# FidoBark.net
KiCad netlist of a schematic drawn in EAGLE
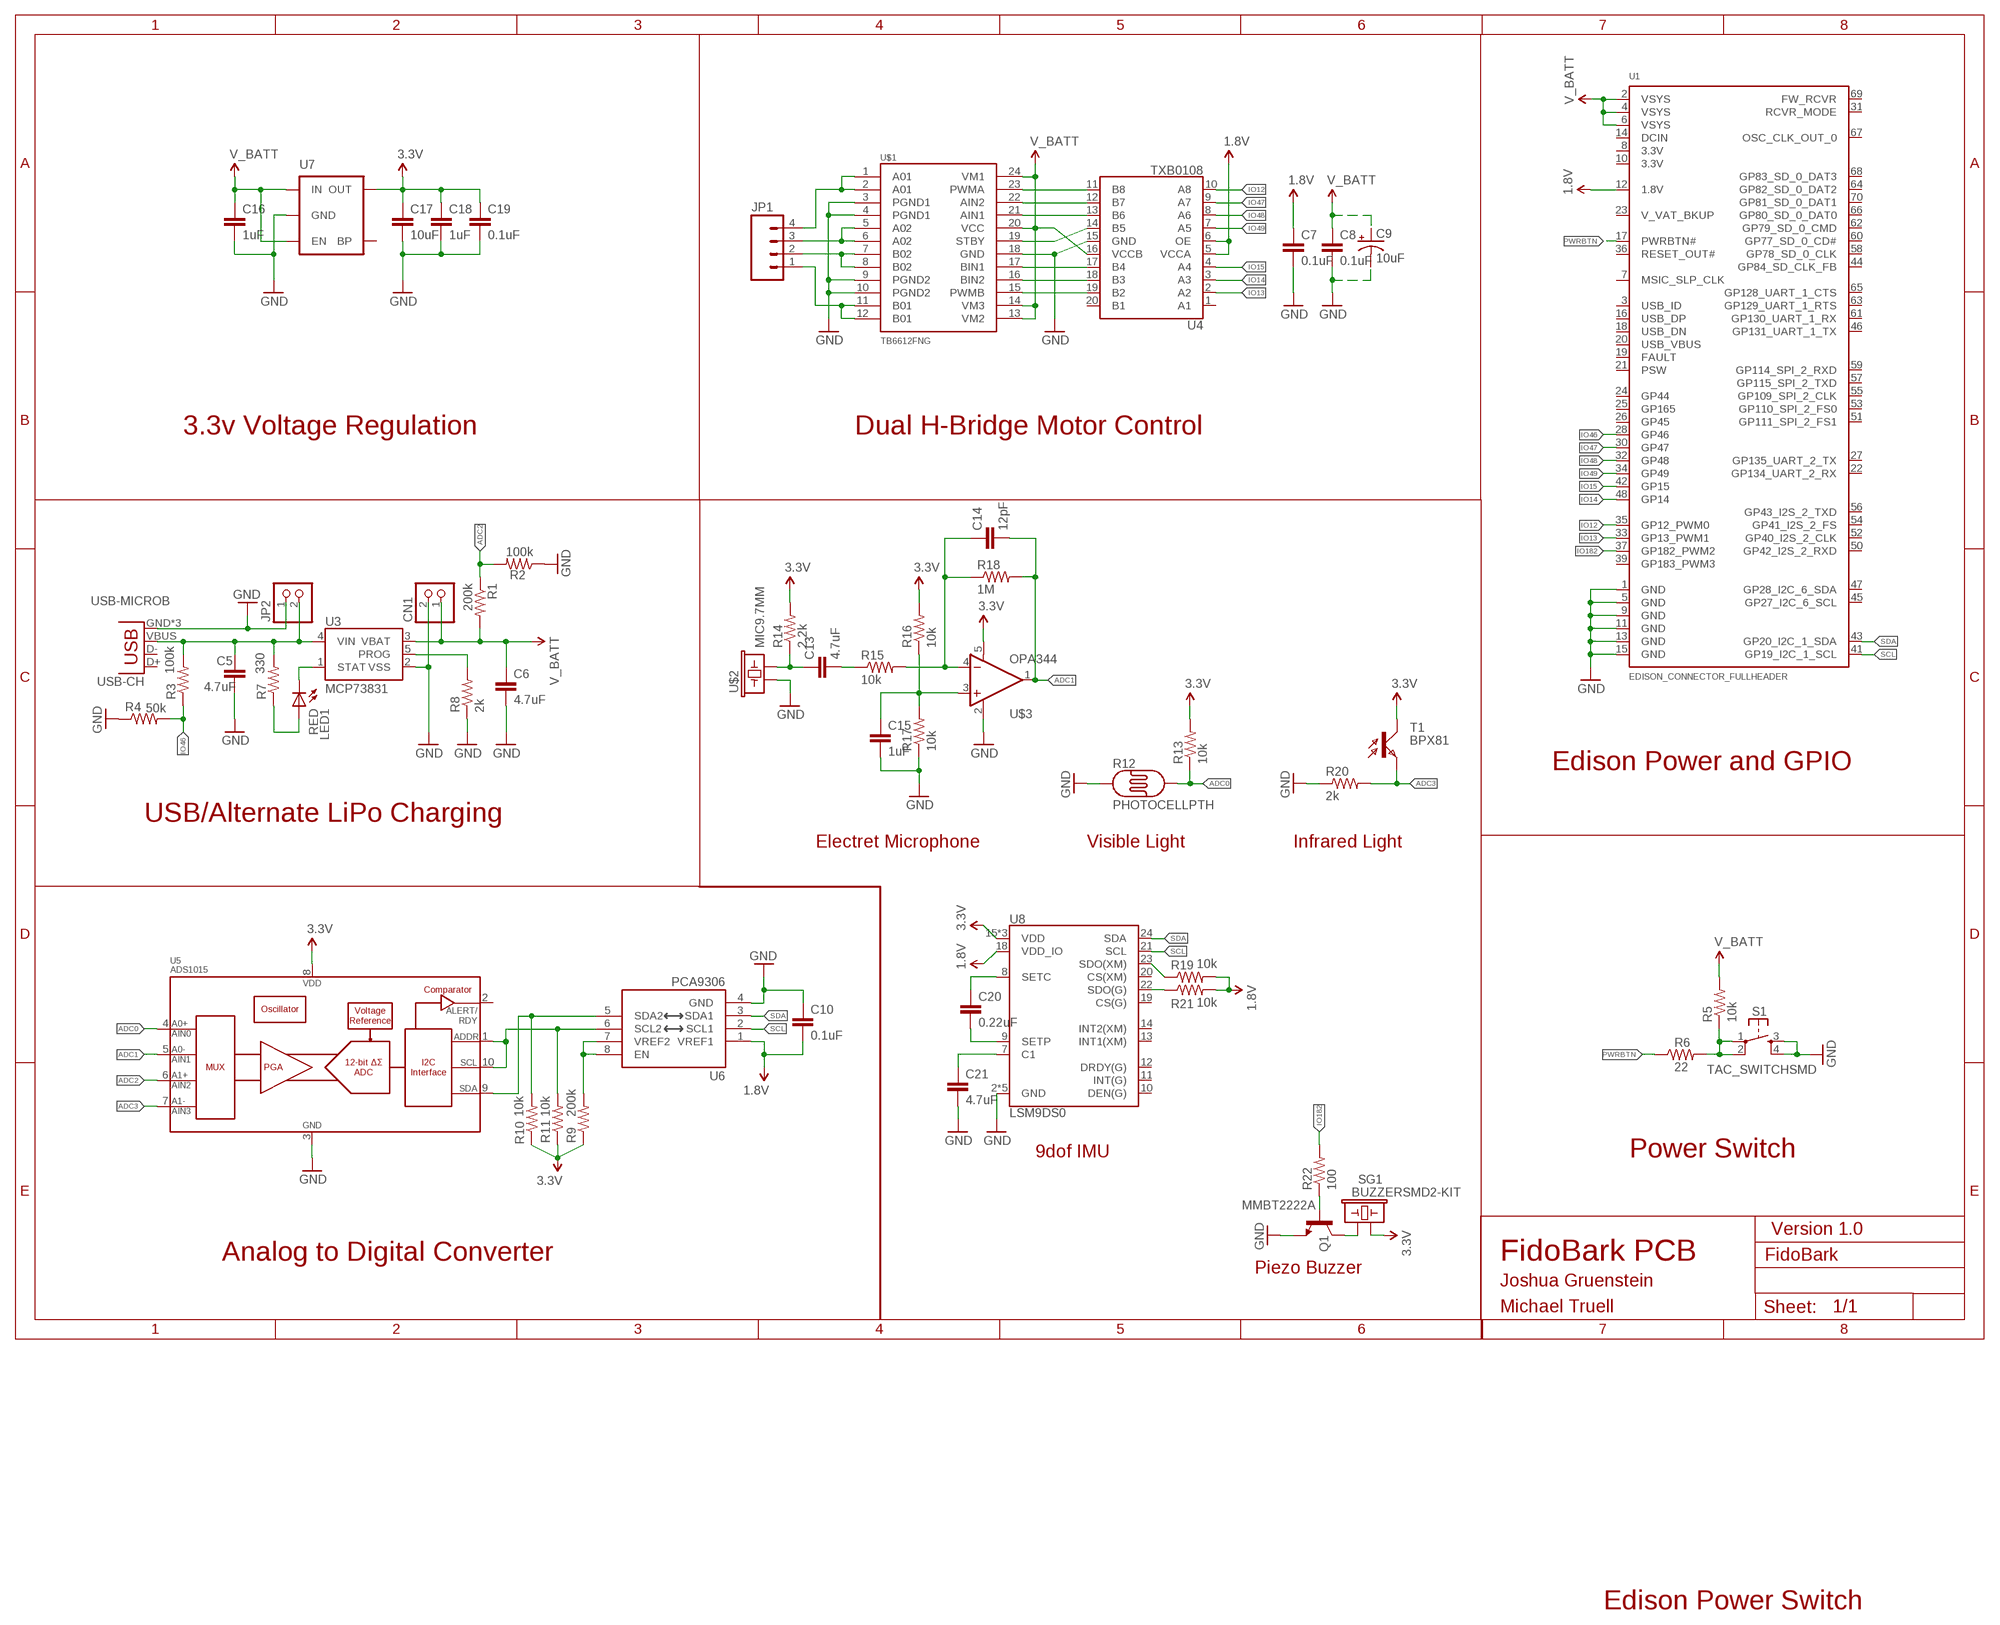
[diagram p0: schematic, sheet 1]

(export (version "E")
  (design (tool "Eeschema 10.0.6"))
  (components
    (comp (ref "C5")
      (value "4.7uF")
      (footprint "eagle-import:0603-CAP")
      (libsource (lib "eagle-import") (part "SparkFun-Passives_CAP0603-CAP"))
    )
    (comp (ref "C6")
      (value "4.7uF")
      (footprint "eagle-import:0603-CAP")
      (libsource (lib "eagle-import") (part "SparkFun-Passives_CAP0603-CAP"))
    )
    (comp (ref "C7")
      (value "0.1uF")
      (footprint "eagle-import:0603-CAP")
      (libsource (lib "eagle-import") (part "CAP0603-CAP"))
    )
    (comp (ref "C8")
      (value "0.1uF")
      (footprint "eagle-import:0603-CAP")
      (libsource (lib "eagle-import") (part "CAP0603-CAP"))
    )
    (comp (ref "C9")
      (value "10uF")
      (footprint "eagle-import:EIA3216")
      (libsource (lib "eagle-import") (part "CAP_POL1206"))
    )
    (comp (ref "C10")
      (value "0.1uF")
      (footprint "eagle-import:0603-CAP")
      (libsource (lib "eagle-import") (part "SparkFun-Passives_CAP0603-CAP"))
    )
    (comp (ref "C13")
      (value "4.7uF")
      (footprint "eagle-import:0603-CAP")
      (libsource (lib "eagle-import") (part "SparkFun-Passives_CAP0603-CAP"))
    )
    (comp (ref "C14")
      (value "12pF")
      (footprint "eagle-import:0603-CAP")
      (libsource (lib "eagle-import") (part "SparkFun-Passives_CAP0603-CAP"))
    )
    (comp (ref "C15")
      (value "1uF")
      (footprint "eagle-import:0603-CAP")
      (libsource (lib "eagle-import") (part "SparkFun-Passives_CAP0603-CAP"))
    )
    (comp (ref "C16")
      (value "1uF")
      (footprint "eagle-import:0603-CAP")
      (libsource (lib "eagle-import") (part "SparkFun-Passives_CAP0603-CAP"))
    )
    (comp (ref "C17")
      (value "10uF")
      (footprint "eagle-import:0603-CAP")
      (libsource (lib "eagle-import") (part "SparkFun-Passives_CAP0603-CAP"))
    )
    (comp (ref "C18")
      (value "1uF")
      (footprint "eagle-import:0603-CAP")
      (libsource (lib "eagle-import") (part "SparkFun-Passives_CAP0603-CAP"))
    )
    (comp (ref "C19")
      (value "0.1uF")
      (footprint "eagle-import:0603-CAP")
      (libsource (lib "eagle-import") (part "SparkFun-Passives_CAP0603-CAP"))
    )
    (comp (ref "C20")
      (value "0.22uF")
      (footprint "eagle-import:0603-CAP")
      (libsource (lib "eagle-import") (part "SparkFun-Passives_CAP0603-CAP"))
    )
    (comp (ref "C21")
      (value "4.7uF")
      (footprint "eagle-import:0603-CAP")
      (libsource (lib "eagle-import") (part "SparkFun-Passives_CAP0603-CAP"))
    )
    (comp (ref "CN1")
      (value "JST_2PIN-SMT-RA")
      (footprint "eagle-import:JST-PH-2-SMT-RA")
      (libsource (lib "eagle-import") (part "JST_2PIN-SMT-RA"))
    )
    (comp (ref "JP1")
      (value "M04PTH")
      (footprint "eagle-import:1X04")
      (libsource (lib "eagle-import") (part "M04PTH"))
    )
    (comp (ref "JP2")
      (value "PINHD-1X2")
      (footprint "eagle-import:1X02")
      (libsource (lib "eagle-import") (part "PINHD-1X2"))
    )
    (comp (ref "LED1")
      (value "RED")
      (footprint "eagle-import:CHIP-LED0603")
      (libsource (lib "eagle-import") (part "LEDCHIP-LED0603"))
    )
    (comp (ref "Q1")
      (value "MMBT2222A")
      (footprint "eagle-import:SOT23-3")
      (libsource (lib "eagle-import") (part "TRANSISTOR_NPNMMBT2222A"))
    )
    (comp (ref "R1")
      (value "200k")
      (footprint "eagle-import:R0603")
      (libsource (lib "eagle-import") (part "R-US_R0603"))
    )
    (comp (ref "R2")
      (value "100k")
      (footprint "eagle-import:R0603")
      (libsource (lib "eagle-import") (part "R-US_R0603"))
    )
    (comp (ref "R3")
      (value "100k")
      (footprint "eagle-import:R0603")
      (libsource (lib "eagle-import") (part "R-US_R0603"))
    )
    (comp (ref "R4")
      (value "50k")
      (footprint "eagle-import:R0603")
      (libsource (lib "eagle-import") (part "R-US_R0603"))
    )
    (comp (ref "R5")
      (value "10k")
      (footprint "eagle-import:R0603")
      (libsource (lib "eagle-import") (part "R-US_R0603"))
    )
    (comp (ref "R6")
      (value "22")
      (footprint "eagle-import:R0603")
      (libsource (lib "eagle-import") (part "R-US_R0603"))
    )
    (comp (ref "R7")
      (value "330")
      (footprint "eagle-import:R0603")
      (libsource (lib "eagle-import") (part "R-US_R0603"))
    )
    (comp (ref "R8")
      (value "2k")
      (footprint "eagle-import:R0603")
      (libsource (lib "eagle-import") (part "R-US_R0603"))
    )
    (comp (ref "R9")
      (value "200k")
      (footprint "eagle-import:R0603")
      (libsource (lib "eagle-import") (part "R-US_R0603"))
    )
    (comp (ref "R10")
      (value "10k")
      (footprint "eagle-import:R0603")
      (libsource (lib "eagle-import") (part "R-US_R0603"))
    )
    (comp (ref "R11")
      (value "10k")
      (footprint "eagle-import:R0603")
      (libsource (lib "eagle-import") (part "R-US_R0603"))
    )
    (comp (ref "R12")
      (value "PHOTOCELLPTH")
      (footprint "eagle-import:PHOTOCELL")
      (libsource (lib "eagle-import") (part "PHOTOCELLPTH"))
    )
    (comp (ref "R13")
      (value "10k")
      (footprint "eagle-import:R0603")
      (libsource (lib "eagle-import") (part "R-US_R0603"))
    )
    (comp (ref "R14")
      (value "2.2k")
      (footprint "eagle-import:R0603")
      (libsource (lib "eagle-import") (part "R-US_R0603"))
    )
    (comp (ref "R15")
      (value "10k")
      (footprint "eagle-import:R0603")
      (libsource (lib "eagle-import") (part "R-US_R0603"))
    )
    (comp (ref "R16")
      (value "10k")
      (footprint "eagle-import:R0603")
      (libsource (lib "eagle-import") (part "R-US_R0603"))
    )
    (comp (ref "R17")
      (value "10k")
      (footprint "eagle-import:R0603")
      (libsource (lib "eagle-import") (part "R-US_R0603"))
    )
    (comp (ref "R18")
      (value "1M")
      (footprint "eagle-import:R0603")
      (libsource (lib "eagle-import") (part "R-US_R0603"))
    )
    (comp (ref "R19")
      (value "10k")
      (footprint "eagle-import:R0603")
      (libsource (lib "eagle-import") (part "R-US_R0603"))
    )
    (comp (ref "R20")
      (value "2k")
      (footprint "eagle-import:R0603")
      (libsource (lib "eagle-import") (part "R-US_R0603"))
    )
    (comp (ref "R21")
      (value "10k")
      (footprint "eagle-import:R0603")
      (libsource (lib "eagle-import") (part "R-US_R0603"))
    )
    (comp (ref "R22")
      (value "100")
      (footprint "eagle-import:R0603")
      (libsource (lib "eagle-import") (part "R-US_R0603"))
    )
    (comp (ref "S1")
      (value "TAC_SWITCHSMD")
      (footprint "eagle-import:TACTILE-SWITCH-SMD")
      (libsource (lib "eagle-import") (part "TAC_SWITCHSMD"))
    )
    (comp (ref "SG1")
      (value "BUZZERSMD2-KIT")
      (footprint "eagle-import:BUZZER-CCV-KIT")
      (libsource (lib "eagle-import") (part "BUZZERSMD2-KIT"))
    )
    (comp (ref "T1")
      (value "BPX81")
      (footprint "eagle-import:BPX81")
      (libsource (lib "eagle-import") (part "BPX81"))
    )
    (comp (ref "U$1")
      (value "TB6612FNG")
      (footprint "eagle-import:SSOP24")
      (libsource (lib "eagle-import") (part "TB6612FNG"))
    )
    (comp (ref "U$2")
      (value "MIC9.7MM")
      (footprint "eagle-import:MIC-9.7MM")
      (libsource (lib "eagle-import") (part "MIC9.7MM"))
    )
    (comp (ref "U$3")
      (value "OPA344")
      (footprint "eagle-import:SOT23-5")
      (libsource (lib "eagle-import") (part "OPA344"))
    )
    (comp (ref "U1")
      (value "EDISON_CONNECTOR_FULLHEADER")
      (footprint "eagle-import:DF40C-70DP-0.4(51)")
      (libsource (lib "eagle-import") (part "EDISON_CONNECTOR_FULLHEADER"))
    )
    (comp (ref "U3")
      (value "MCP73831")
      (footprint "eagle-import:SOT23-5")
      (libsource (lib "eagle-import") (part "MCP73831"))
    )
    (comp (ref "U4")
      (value "TXB0108")
      (footprint "eagle-import:UFDFN-20")
      (libsource (lib "eagle-import") (part "TXB0108"))
    )
    (comp (ref "U5")
      (value "ADS1015")
      (footprint "eagle-import:MSOP10")
      (libsource (lib "eagle-import") (part "ADS1015"))
    )
    (comp (ref "U6")
      (value "PCA9306")
      (footprint "eagle-import:PSOP-8")
      (libsource (lib "eagle-import") (part "PCA9306"))
    )
    (comp (ref "U7")
      (value "MIC52053.3V")
      (footprint "eagle-import:SOT23-5")
      (libsource (lib "eagle-import") (part "MIC52053.3V"))
    )
    (comp (ref "U8")
      (value "LSM9DS0")
      (footprint "eagle-import:LGA-24")
      (libsource (lib "eagle-import") (part "LSM9DS0"))
    )
    (comp (ref "USB-CH")
      (value "USB-MICROB")
      (footprint "eagle-import:USB-MICROB")
      (libsource (lib "eagle-import") (part "USB-MICROB"))
    )
  )
  (nets
    (net (code "1") (name "1.8V") (class "Default")
      (node (ref "C10") (pin "2") (pinfunction "2_2") (pintype "passive"))
      (node (ref "C7") (pin "1") (pinfunction "1_1") (pintype "passive"))
      (node (ref "R19") (pin "2") (pinfunction "2_2") (pintype "passive"))
      (node (ref "R21") (pin "2") (pinfunction "2_2") (pintype "passive"))
      (node (ref "U1") (pin "12") (pinfunction "1.8V_12") (pintype "bidirectional"))
      (node (ref "U4") (pin "5") (pinfunction "VCCA_5") (pintype "bidirectional"))
      (node (ref "U4") (pin "6") (pinfunction "OE_6") (pintype "bidirectional"))
      (node (ref "U6") (pin "1") (pinfunction "VREF1_1") (pintype "bidirectional"))
      (node (ref "U8") (pin "18") (pinfunction "VDD_IO_18") (pintype "bidirectional"))
    )
    (net (code "2") (name "3.3V") (class "Default")
      (node (ref "C17") (pin "1") (pinfunction "1_1") (pintype "passive"))
      (node (ref "C18") (pin "1") (pinfunction "1_1") (pintype "passive"))
      (node (ref "C19") (pin "1") (pinfunction "1_1") (pintype "passive"))
      (node (ref "R10") (pin "1") (pinfunction "1_1") (pintype "passive"))
      (node (ref "R11") (pin "1") (pinfunction "1_1") (pintype "passive"))
      (node (ref "R13") (pin "2") (pinfunction "2_2") (pintype "passive"))
      (node (ref "R14") (pin "2") (pinfunction "2_2") (pintype "passive"))
      (node (ref "R16") (pin "2") (pinfunction "2_2") (pintype "passive"))
      (node (ref "R9") (pin "1") (pinfunction "1_1") (pintype "passive"))
      (node (ref "SG1") (pin "-") (pinfunction "2_-") (pintype "passive"))
      (node (ref "T1") (pin "C") (pinfunction "C_C") (pintype "passive"))
      (node (ref "U$3") (pin "5") (pinfunction "V+_5") (pintype "power_in"))
      (node (ref "U5") (pin "8") (pinfunction "VDD_8") (pintype "bidirectional"))
      (node (ref "U7") (pin "5") (pinfunction "OUT_5") (pintype "passive"))
      (node (ref "U8") (pin "15") (pinfunction "VDD_15") (pintype "bidirectional"))
      (node (ref "U8") (pin "16") (pinfunction "VDD_16") (pintype "bidirectional"))
      (node (ref "U8") (pin "17") (pinfunction "VDD_17") (pintype "bidirectional"))
    )
    (net (code "3") (name "ADC0") (class "Default")
      (node (ref "R12") (pin "2") (pinfunction "P$2_2") (pintype "bidirectional"))
      (node (ref "R13") (pin "1") (pinfunction "1_1") (pintype "passive"))
      (node (ref "U5") (pin "4") (pinfunction "AIN0_4") (pintype "bidirectional"))
    )
    (net (code "4") (name "ADC1") (class "Default")
      (node (ref "C14") (pin "2") (pinfunction "2_2") (pintype "passive"))
      (node (ref "R18") (pin "2") (pinfunction "2_2") (pintype "passive"))
      (node (ref "U$3") (pin "1") (pinfunction "OUT_1") (pintype "output"))
      (node (ref "U5") (pin "5") (pinfunction "AIN1_5") (pintype "bidirectional"))
    )
    (net (code "5") (name "ADC2") (class "Default")
      (node (ref "R1") (pin "1") (pinfunction "1_1") (pintype "passive"))
      (node (ref "R2") (pin "2") (pinfunction "2_2") (pintype "passive"))
      (node (ref "U5") (pin "6") (pinfunction "AIN2_6") (pintype "bidirectional"))
    )
    (net (code "6") (name "ADC3") (class "Default")
      (node (ref "R20") (pin "2") (pinfunction "2_2") (pintype "passive"))
      (node (ref "T1") (pin "E") (pinfunction "E_E") (pintype "passive"))
      (node (ref "U5") (pin "7") (pinfunction "AIN3_7") (pintype "bidirectional"))
    )
    (net (code "7") (name "GND") (class "Default")
      (node (ref "C10") (pin "1") (pinfunction "1_1") (pintype "passive"))
      (node (ref "C15") (pin "2") (pinfunction "2_2") (pintype "passive"))
      (node (ref "C16") (pin "2") (pinfunction "2_2") (pintype "passive"))
      (node (ref "C17") (pin "2") (pinfunction "2_2") (pintype "passive"))
      (node (ref "C18") (pin "2") (pinfunction "2_2") (pintype "passive"))
      (node (ref "C19") (pin "2") (pinfunction "2_2") (pintype "passive"))
      (node (ref "C21") (pin "2") (pinfunction "2_2") (pintype "passive"))
      (node (ref "C5") (pin "2") (pinfunction "2_2") (pintype "passive"))
      (node (ref "C6") (pin "2") (pinfunction "2_2") (pintype "passive"))
      (node (ref "C7") (pin "2") (pinfunction "2_2") (pintype "passive"))
      (node (ref "C8") (pin "2") (pinfunction "2_2") (pintype "passive"))
      (node (ref "C9") (pin "C") (pinfunction "-_C") (pintype "passive"))
      (node (ref "CN1") (pin "2") (pinfunction "1_2") (pintype "passive"))
      (node (ref "JP2") (pin "1") (pinfunction "1_1") (pintype "passive"))
      (node (ref "Q1") (pin "2") (pinfunction "E_2") (pintype "passive"))
      (node (ref "R12") (pin "1") (pinfunction "P$1_1") (pintype "bidirectional"))
      (node (ref "R17") (pin "1") (pinfunction "1_1") (pintype "passive"))
      (node (ref "R2") (pin "1") (pinfunction "1_1") (pintype "passive"))
      (node (ref "R20") (pin "1") (pinfunction "1_1") (pintype "passive"))
      (node (ref "R4") (pin "1") (pinfunction "1_1") (pintype "passive"))
      (node (ref "R8") (pin "1") (pinfunction "1_1") (pintype "passive"))
      (node (ref "S1") (pin "3") (pinfunction "3_3") (pintype "passive"))
      (node (ref "S1") (pin "4") (pinfunction "4_4") (pintype "passive"))
      (node (ref "U$1") (pin "10") (pinfunction "PGND2_10") (pintype "bidirectional"))
      (node (ref "U$1") (pin "18") (pinfunction "GND_18") (pintype "bidirectional"))
      (node (ref "U$1") (pin "3") (pinfunction "PGND1_3") (pintype "bidirectional"))
      (node (ref "U$1") (pin "4") (pinfunction "PGND1_4") (pintype "bidirectional"))
      (node (ref "U$1") (pin "9") (pinfunction "PGND2_9") (pintype "bidirectional"))
      (node (ref "U$2") (pin "1") (pinfunction "1_1") (pintype "passive"))
      (node (ref "U$3") (pin "2") (pinfunction "V-_2") (pintype "power_in"))
      (node (ref "U1") (pin "1") (pinfunction "GND_1") (pintype "bidirectional"))
      (node (ref "U1") (pin "11") (pinfunction "GND_11") (pintype "bidirectional"))
      (node (ref "U1") (pin "13") (pinfunction "GND_13") (pintype "bidirectional"))
      (node (ref "U1") (pin "15") (pinfunction "GND_15") (pintype "bidirectional"))
      (node (ref "U1") (pin "5") (pinfunction "GND_5") (pintype "bidirectional"))
      (node (ref "U1") (pin "9") (pinfunction "GND_9") (pintype "bidirectional"))
      (node (ref "U3") (pin "2") (pinfunction "VSS_2") (pintype "power_in"))
      (node (ref "U4") (pin "15") (pinfunction "GND_15") (pintype "bidirectional"))
      (node (ref "U5") (pin "3") (pinfunction "VSS_3") (pintype "bidirectional"))
      (node (ref "U6") (pin "4") (pinfunction "GND_4") (pintype "bidirectional"))
      (node (ref "U7") (pin "2") (pinfunction "GND_2") (pintype "input"))
      (node (ref "U8") (pin "2") (pinfunction "GND_2") (pintype "bidirectional"))
      (node (ref "U8") (pin "3") (pinfunction "GND_3") (pintype "bidirectional"))
      (node (ref "U8") (pin "4") (pinfunction "GND_4") (pintype "bidirectional"))
      (node (ref "U8") (pin "5") (pinfunction "GND_5") (pintype "bidirectional"))
      (node (ref "U8") (pin "6") (pinfunction "GND_6") (pintype "bidirectional"))
      (node (ref "USB-CH") (pin "GND") (pinfunction "GND_GND") (pintype "bidirectional"))
      (node (ref "USB-CH") (pin "MT1") (pinfunction "GND_MT1") (pintype "bidirectional"))
      (node (ref "USB-CH") (pin "MT2") (pinfunction "GND_MT2") (pintype "bidirectional"))
    )
    (net (code "8") (name "IO12") (class "Default")
      (node (ref "U1") (pin "35") (pinfunction "GP12_PWM0_35") (pintype "bidirectional"))
      (node (ref "U4") (pin "10") (pinfunction "A8_10") (pintype "bidirectional"))
    )
    (net (code "9") (name "IO13") (class "Default")
      (node (ref "U1") (pin "33") (pinfunction "GP13_PWM1_33") (pintype "bidirectional"))
      (node (ref "U4") (pin "2") (pinfunction "A2_2") (pintype "bidirectional"))
    )
    (net (code "10") (name "IO14") (class "Default")
      (node (ref "U1") (pin "48") (pinfunction "GP14_48") (pintype "bidirectional"))
      (node (ref "U4") (pin "3") (pinfunction "A3_3") (pintype "bidirectional"))
    )
    (net (code "11") (name "IO15") (class "Default")
      (node (ref "U1") (pin "42") (pinfunction "GP15_42") (pintype "bidirectional"))
      (node (ref "U4") (pin "4") (pinfunction "A4_4") (pintype "bidirectional"))
    )
    (net (code "12") (name "IO46") (class "Default")
      (node (ref "R3") (pin "1") (pinfunction "1_1") (pintype "passive"))
      (node (ref "R4") (pin "2") (pinfunction "2_2") (pintype "passive"))
      (node (ref "U1") (pin "28") (pinfunction "GP46_28") (pintype "bidirectional"))
    )
    (net (code "13") (name "IO47") (class "Default")
      (node (ref "U1") (pin "30") (pinfunction "GP47_30") (pintype "bidirectional"))
      (node (ref "U4") (pin "9") (pinfunction "A7_9") (pintype "bidirectional"))
    )
    (net (code "14") (name "IO48") (class "Default")
      (node (ref "U1") (pin "32") (pinfunction "GP48_32") (pintype "bidirectional"))
      (node (ref "U4") (pin "8") (pinfunction "A6_8") (pintype "bidirectional"))
    )
    (net (code "15") (name "IO49") (class "Default")
      (node (ref "U1") (pin "34") (pinfunction "GP49_34") (pintype "bidirectional"))
      (node (ref "U4") (pin "7") (pinfunction "A5_7") (pintype "bidirectional"))
    )
    (net (code "16") (name "IO182") (class "Default")
      (node (ref "R22") (pin "2") (pinfunction "2_2") (pintype "passive"))
      (node (ref "U1") (pin "37") (pinfunction "GP182_PWM2_37") (pintype "bidirectional"))
    )
    (net (code "17") (name "Net-(C13-Pad1)") (class "Default")
      (node (ref "C13") (pin "1") (pinfunction "1_1") (pintype "passive"))
      (node (ref "R14") (pin "1") (pinfunction "1_1") (pintype "passive"))
      (node (ref "U$2") (pin "2") (pinfunction "2_2") (pintype "passive"))
    )
    (net (code "18") (name "Net-(C13-Pad2)") (class "Default")
      (node (ref "C13") (pin "2") (pinfunction "2_2") (pintype "passive"))
      (node (ref "R15") (pin "1") (pinfunction "1_1") (pintype "passive"))
    )
    (net (code "19") (name "Net-(JP1-Pad1)") (class "Default")
      (node (ref "JP1") (pin "1") (pinfunction "1_1") (pintype "passive"))
      (node (ref "U$1") (pin "11") (pinfunction "B01_11") (pintype "bidirectional"))
      (node (ref "U$1") (pin "12") (pinfunction "B01_12") (pintype "bidirectional"))
    )
    (net (code "20") (name "Net-(JP1-Pad2)") (class "Default")
      (node (ref "JP1") (pin "2") (pinfunction "2_2") (pintype "passive"))
      (node (ref "U$1") (pin "7") (pinfunction "B02_7") (pintype "bidirectional"))
      (node (ref "U$1") (pin "8") (pinfunction "B02_8") (pintype "bidirectional"))
    )
    (net (code "21") (name "Net-(JP1-Pad3)") (class "Default")
      (node (ref "JP1") (pin "3") (pinfunction "3_3") (pintype "passive"))
      (node (ref "U$1") (pin "5") (pinfunction "A02_5") (pintype "bidirectional"))
      (node (ref "U$1") (pin "6") (pinfunction "A02_6") (pintype "bidirectional"))
    )
    (net (code "22") (name "Net-(JP1-Pad4)") (class "Default")
      (node (ref "JP1") (pin "4") (pinfunction "4_4") (pintype "passive"))
      (node (ref "U$1") (pin "1") (pinfunction "A01_1") (pintype "bidirectional"))
      (node (ref "U$1") (pin "2") (pinfunction "A01_2") (pintype "bidirectional"))
    )
    (net (code "23") (name "Net-(LED1-PadA)") (class "Default")
      (node (ref "LED1") (pin "A") (pinfunction "A_A") (pintype "passive"))
      (node (ref "R7") (pin "1") (pinfunction "1_1") (pintype "passive"))
    )
    (net (code "24") (name "Net-(Q1-B)") (class "Default")
      (node (ref "Q1") (pin "1") (pinfunction "B_1") (pintype "passive"))
      (node (ref "R22") (pin "1") (pinfunction "1_1") (pintype "passive"))
    )
    (net (code "25") (name "Net-(Q1-C)") (class "Default")
      (node (ref "Q1") (pin "3") (pinfunction "C_3") (pintype "passive"))
      (node (ref "SG1") (pin "+") (pinfunction "1_+") (pintype "passive"))
    )
    (net (code "26") (name "Net-(R5-Pad1)") (class "Default")
      (node (ref "R5") (pin "1") (pinfunction "1_1") (pintype "passive"))
      (node (ref "R6") (pin "2") (pinfunction "2_2") (pintype "passive"))
      (node (ref "S1") (pin "1") (pinfunction "1_1") (pintype "passive"))
      (node (ref "S1") (pin "2") (pinfunction "2_2") (pintype "passive"))
    )
    (net (code "27") (name "Net-(U$1-AIN1)") (class "Default")
      (node (ref "U$1") (pin "21") (pinfunction "AIN1_21") (pintype "bidirectional"))
      (node (ref "U4") (pin "13") (pinfunction "B6_13") (pintype "bidirectional"))
    )
    (net (code "28") (name "Net-(U$1-AIN2)") (class "Default")
      (node (ref "U$1") (pin "22") (pinfunction "AIN2_22") (pintype "bidirectional"))
      (node (ref "U4") (pin "12") (pinfunction "B7_12") (pintype "bidirectional"))
    )
    (net (code "29") (name "Net-(U$1-BIN1)") (class "Default")
      (node (ref "U$1") (pin "17") (pinfunction "BIN1_17") (pintype "bidirectional"))
      (node (ref "U4") (pin "17") (pinfunction "B4_17") (pintype "bidirectional"))
    )
    (net (code "30") (name "Net-(U$1-BIN2)") (class "Default")
      (node (ref "U$1") (pin "16") (pinfunction "BIN2_16") (pintype "bidirectional"))
      (node (ref "U4") (pin "18") (pinfunction "B3_18") (pintype "bidirectional"))
    )
    (net (code "31") (name "Net-(U$1-PWMA)") (class "Default")
      (node (ref "U$1") (pin "23") (pinfunction "PWMA_23") (pintype "bidirectional"))
      (node (ref "U4") (pin "11") (pinfunction "B8_11") (pintype "bidirectional"))
    )
    (net (code "32") (name "Net-(U$1-PWMB)") (class "Default")
      (node (ref "U$1") (pin "15") (pinfunction "PWMB_15") (pintype "bidirectional"))
      (node (ref "U4") (pin "19") (pinfunction "B2_19") (pintype "bidirectional"))
    )
    (net (code "33") (name "Net-(U$1-STBY)") (class "Default")
      (node (ref "U$1") (pin "19") (pinfunction "STBY_19") (pintype "bidirectional"))
      (node (ref "U4") (pin "14") (pinfunction "B5_14") (pintype "bidirectional"))
    )
    (net (code "34") (name "Net-(U$3-+IN)") (class "Default")
      (node (ref "C15") (pin "1") (pinfunction "1_1") (pintype "passive"))
      (node (ref "R16") (pin "1") (pinfunction "1_1") (pintype "passive"))
      (node (ref "R17") (pin "2") (pinfunction "2_2") (pintype "passive"))
      (node (ref "U$3") (pin "3") (pinfunction "+IN_3") (pintype "input"))
    )
    (net (code "35") (name "Net-(U$3--IN)") (class "Default")
      (node (ref "C14") (pin "1") (pinfunction "1_1") (pintype "passive"))
      (node (ref "R15") (pin "2") (pinfunction "2_2") (pintype "passive"))
      (node (ref "R18") (pin "1") (pinfunction "1_1") (pintype "passive"))
      (node (ref "U$3") (pin "4") (pinfunction "-IN_4") (pintype "input"))
    )
    (net (code "36") (name "Net-(U3-PROG)") (class "Default")
      (node (ref "R8") (pin "2") (pinfunction "2_2") (pintype "passive"))
      (node (ref "U3") (pin "5") (pinfunction "PROG_5") (pintype "input"))
    )
    (net (code "37") (name "Net-(U3-STAT)") (class "Default")
      (node (ref "LED1") (pin "C") (pinfunction "C_C") (pintype "passive"))
      (node (ref "U3") (pin "1") (pinfunction "STAT_1") (pintype "output"))
    )
    (net (code "38") (name "Net-(U3-VIN)") (class "Default")
      (node (ref "C5") (pin "1") (pinfunction "1_1") (pintype "passive"))
      (node (ref "JP2") (pin "2") (pinfunction "2_2") (pintype "passive"))
      (node (ref "R3") (pin "2") (pinfunction "2_2") (pintype "passive"))
      (node (ref "R7") (pin "2") (pinfunction "2_2") (pintype "passive"))
      (node (ref "U3") (pin "4") (pinfunction "VIN_4") (pintype "power_in"))
      (node (ref "USB-CH") (pin "VBUS") (pinfunction "VBUS_VBUS") (pintype "bidirectional"))
    )
    (net (code "39") (name "Net-(U5-ADDR)") (class "Default")
      (node (ref "R11") (pin "2") (pinfunction "2_2") (pintype "passive"))
      (node (ref "U5") (pin "1") (pinfunction "ADDR_1") (pintype "bidirectional"))
      (node (ref "U5") (pin "10") (pinfunction "SCL_10") (pintype "bidirectional"))
      (node (ref "U6") (pin "6") (pinfunction "SCL2_6") (pintype "bidirectional"))
    )
    (net (code "40") (name "Net-(U5-SDA)") (class "Default")
      (node (ref "R10") (pin "2") (pinfunction "2_2") (pintype "passive"))
      (node (ref "U5") (pin "9") (pinfunction "SDA_9") (pintype "bidirectional"))
      (node (ref "U6") (pin "5") (pinfunction "SDA2_5") (pintype "bidirectional"))
    )
    (net (code "41") (name "Net-(U6-EN)") (class "Default")
      (node (ref "R9") (pin "2") (pinfunction "2_2") (pintype "passive"))
      (node (ref "U6") (pin "7") (pinfunction "VREF2_7") (pintype "bidirectional"))
      (node (ref "U6") (pin "8") (pinfunction "EN_8") (pintype "bidirectional"))
    )
    (net (code "42") (name "Net-(U8-C1)") (class "Default")
      (node (ref "C21") (pin "1") (pinfunction "1_1") (pintype "passive"))
      (node (ref "U8") (pin "7") (pinfunction "C1_7") (pintype "bidirectional"))
    )
    (net (code "43") (name "Net-(U8-SDO(G))") (class "Default")
      (node (ref "R21") (pin "1") (pinfunction "1_1") (pintype "passive"))
      (node (ref "U8") (pin "22") (pinfunction "SDO(G)_22") (pintype "bidirectional"))
    )
    (net (code "44") (name "Net-(U8-SDO(XM))") (class "Default")
      (node (ref "R19") (pin "1") (pinfunction "1_1") (pintype "passive"))
      (node (ref "U8") (pin "23") (pinfunction "SDO(XM)_23") (pintype "bidirectional"))
    )
    (net (code "45") (name "Net-(U8-SETC)") (class "Default")
      (node (ref "C20") (pin "1") (pinfunction "1_1") (pintype "passive"))
      (node (ref "U8") (pin "8") (pinfunction "SETC_8") (pintype "bidirectional"))
    )
    (net (code "46") (name "Net-(U8-SETP)") (class "Default")
      (node (ref "C20") (pin "2") (pinfunction "2_2") (pintype "passive"))
      (node (ref "U8") (pin "9") (pinfunction "SETP_9") (pintype "bidirectional"))
    )
    (net (code "47") (name "PWRBTN") (class "Default")
      (node (ref "R6") (pin "1") (pinfunction "1_1") (pintype "passive"))
      (node (ref "U1") (pin "17") (pinfunction "PWRBTN#_17") (pintype "bidirectional"))
    )
    (net (code "48") (name "SCL") (class "Default")
      (node (ref "U1") (pin "41") (pinfunction "GP19_I2C_1_SCL_41") (pintype "bidirectional"))
      (node (ref "U6") (pin "2") (pinfunction "SCL1_2") (pintype "bidirectional"))
      (node (ref "U8") (pin "21") (pinfunction "SCL_21") (pintype "bidirectional"))
    )
    (net (code "49") (name "SDA") (class "Default")
      (node (ref "U1") (pin "43") (pinfunction "GP20_I2C_1_SDA_43") (pintype "bidirectional"))
      (node (ref "U6") (pin "3") (pinfunction "SDA1_3") (pintype "bidirectional"))
      (node (ref "U8") (pin "24") (pinfunction "SDA_24") (pintype "bidirectional"))
    )
    (net (code "50") (name "V_BATT") (class "Default")
      (node (ref "C16") (pin "1") (pinfunction "1_1") (pintype "passive"))
      (node (ref "C6") (pin "1") (pinfunction "1_1") (pintype "passive"))
      (node (ref "C8") (pin "1") (pinfunction "1_1") (pintype "passive"))
      (node (ref "C9") (pin "A") (pinfunction "+_A") (pintype "passive"))
      (node (ref "CN1") (pin "1") (pinfunction "2_1") (pintype "passive"))
      (node (ref "R1") (pin "2") (pinfunction "2_2") (pintype "passive"))
      (node (ref "R5") (pin "2") (pinfunction "2_2") (pintype "passive"))
      (node (ref "U$1") (pin "13") (pinfunction "VM2_13") (pintype "bidirectional"))
      (node (ref "U$1") (pin "14") (pinfunction "VM3_14") (pintype "bidirectional"))
      (node (ref "U$1") (pin "20") (pinfunction "VCC_20") (pintype "bidirectional"))
      (node (ref "U$1") (pin "24") (pinfunction "VM1_24") (pintype "bidirectional"))
      (node (ref "U1") (pin "2") (pinfunction "VSYS_2") (pintype "bidirectional"))
      (node (ref "U1") (pin "4") (pinfunction "VSYS_4") (pintype "bidirectional"))
      (node (ref "U1") (pin "6") (pinfunction "VSYS_6") (pintype "bidirectional"))
      (node (ref "U3") (pin "3") (pinfunction "VBAT_3") (pintype "power_in"))
      (node (ref "U4") (pin "16") (pinfunction "VCCB_16") (pintype "bidirectional"))
      (node (ref "U7") (pin "1") (pinfunction "IN_1") (pintype "input"))
      (node (ref "U7") (pin "3") (pinfunction "EN_3") (pintype "input"))
    )
    (net (code "51") (name "unconnected-(U1-3.3V-Pad8)") (class "Default")
      (node (ref "U1") (pin "8") (pinfunction "3.3V_8") (pintype "bidirectional"))
    )
    (net (code "52") (name "unconnected-(U1-3.3V-Pad10)") (class "Default")
      (node (ref "U1") (pin "10") (pinfunction "3.3V_10") (pintype "bidirectional"))
    )
    (net (code "53") (name "unconnected-(U1-DCIN-Pad14)") (class "Default")
      (node (ref "U1") (pin "14") (pinfunction "DCIN_14") (pintype "bidirectional"))
    )
    (net (code "54") (name "unconnected-(U1-FAULT-Pad19)") (class "Default")
      (node (ref "U1") (pin "19") (pinfunction "FAULT_19") (pintype "bidirectional"))
    )
    (net (code "55") (name "unconnected-(U1-FW_RCVR-Pad69)") (class "Default")
      (node (ref "U1") (pin "69") (pinfunction "FW_RCVR_69") (pintype "bidirectional"))
    )
    (net (code "56") (name "unconnected-(U1-GP27_I2C_6_SCL-Pad45)") (class "Default")
      (node (ref "U1") (pin "45") (pinfunction "GP27_I2C_6_SCL_45") (pintype "bidirectional"))
    )
    (net (code "57") (name "unconnected-(U1-GP28_I2C_6_SDA-Pad47)") (class "Default")
      (node (ref "U1") (pin "47") (pinfunction "GP28_I2C_6_SDA_47") (pintype "bidirectional"))
    )
    (net (code "58") (name "unconnected-(U1-GP40_I2S_2_CLK-Pad52)") (class "Default")
      (node (ref "U1") (pin "52") (pinfunction "GP40_I2S_2_CLK_52") (pintype "bidirectional"))
    )
    (net (code "59") (name "unconnected-(U1-GP41_I2S_2_FS-Pad54)") (class "Default")
      (node (ref "U1") (pin "54") (pinfunction "GP41_I2S_2_FS_54") (pintype "bidirectional"))
    )
    (net (code "60") (name "unconnected-(U1-GP42_I2S_2_RXD-Pad50)") (class "Default")
      (node (ref "U1") (pin "50") (pinfunction "GP42_I2S_2_RXD_50") (pintype "bidirectional"))
    )
    (net (code "61") (name "unconnected-(U1-GP43_I2S_2_TXD-Pad56)") (class "Default")
      (node (ref "U1") (pin "56") (pinfunction "GP43_I2S_2_TXD_56") (pintype "bidirectional"))
    )
    (net (code "62") (name "unconnected-(U1-GP44-Pad24)") (class "Default")
      (node (ref "U1") (pin "24") (pinfunction "GP44_24") (pintype "bidirectional"))
    )
    (net (code "63") (name "unconnected-(U1-GP45-Pad26)") (class "Default")
      (node (ref "U1") (pin "26") (pinfunction "GP45_26") (pintype "bidirectional"))
    )
    (net (code "64") (name "unconnected-(U1-GP77_SD_0_CD#-Pad60)") (class "Default")
      (node (ref "U1") (pin "60") (pinfunction "GP77_SD_0_CD#_60") (pintype "bidirectional"))
    )
    (net (code "65") (name "unconnected-(U1-GP78_SD_0_CLK-Pad58)") (class "Default")
      (node (ref "U1") (pin "58") (pinfunction "GP78_SD_0_CLK_58") (pintype "bidirectional"))
    )
    (net (code "66") (name "unconnected-(U1-GP79_SD_0_CMD-Pad62)") (class "Default")
      (node (ref "U1") (pin "62") (pinfunction "GP79_SD_0_CMD_62") (pintype "bidirectional"))
    )
    (net (code "67") (name "unconnected-(U1-GP80_SD_0_DAT0-Pad66)") (class "Default")
      (node (ref "U1") (pin "66") (pinfunction "GP80_SD_0_DAT0_66") (pintype "bidirectional"))
    )
    (net (code "68") (name "unconnected-(U1-GP81_SD_0_DAT1-Pad70)") (class "Default")
      (node (ref "U1") (pin "70") (pinfunction "GP81_SD_0_DAT1_70") (pintype "bidirectional"))
    )
    (net (code "69") (name "unconnected-(U1-GP82_SD_0_DAT2-Pad64)") (class "Default")
      (node (ref "U1") (pin "64") (pinfunction "GP82_SD_0_DAT2_64") (pintype "bidirectional"))
    )
    (net (code "70") (name "unconnected-(U1-GP83_SD_0_DAT3-Pad68)") (class "Default")
      (node (ref "U1") (pin "68") (pinfunction "GP83_SD_0_DAT3_68") (pintype "bidirectional"))
    )
    (net (code "71") (name "unconnected-(U1-GP84_SD_CLK_FB-Pad44)") (class "Default")
      (node (ref "U1") (pin "44") (pinfunction "GP84_SD_CLK_FB_44") (pintype "bidirectional"))
    )
    (net (code "72") (name "unconnected-(U1-GP109_SPI_2_CLK-Pad55)") (class "Default")
      (node (ref "U1") (pin "55") (pinfunction "GP109_SPI_2_CLK_55") (pintype "bidirectional"))
    )
    (net (code "73") (name "unconnected-(U1-GP110_SPI_2_FS0-Pad53)") (class "Default")
      (node (ref "U1") (pin "53") (pinfunction "GP110_SPI_2_FS0_53") (pintype "bidirectional"))
    )
    (net (code "74") (name "unconnected-(U1-GP111_SPI_2_FS1-Pad51)") (class "Default")
      (node (ref "U1") (pin "51") (pinfunction "GP111_SPI_2_FS1_51") (pintype "bidirectional"))
    )
    (net (code "75") (name "unconnected-(U1-GP114_SPI_2_RXD-Pad59)") (class "Default")
      (node (ref "U1") (pin "59") (pinfunction "GP114_SPI_2_RXD_59") (pintype "bidirectional"))
    )
    (net (code "76") (name "unconnected-(U1-GP115_SPI_2_TXD-Pad57)") (class "Default")
      (node (ref "U1") (pin "57") (pinfunction "GP115_SPI_2_TXD_57") (pintype "bidirectional"))
    )
    (net (code "77") (name "unconnected-(U1-GP128_UART_1_CTS-Pad65)") (class "Default")
      (node (ref "U1") (pin "65") (pinfunction "GP128_UART_1_CTS_65") (pintype "bidirectional"))
    )
    (net (code "78") (name "unconnected-(U1-GP129_UART_1_RTS-Pad63)") (class "Default")
      (node (ref "U1") (pin "63") (pinfunction "GP129_UART_1_RTS_63") (pintype "bidirectional"))
    )
    (net (code "79") (name "unconnected-(U1-GP130_UART_1_RX-Pad61)") (class "Default")
      (node (ref "U1") (pin "61") (pinfunction "GP130_UART_1_RX_61") (pintype "bidirectional"))
    )
    (net (code "80") (name "unconnected-(U1-GP131_UART_1_TX-Pad46)") (class "Default")
      (node (ref "U1") (pin "46") (pinfunction "GP131_UART_1_TX_46") (pintype "bidirectional"))
    )
    (net (code "81") (name "unconnected-(U1-GP134_UART_2_RX-Pad22)") (class "Default")
      (node (ref "U1") (pin "22") (pinfunction "GP134_UART_2_RX_22") (pintype "bidirectional"))
    )
    (net (code "82") (name "unconnected-(U1-GP135_UART_2_TX-Pad27)") (class "Default")
      (node (ref "U1") (pin "27") (pinfunction "GP135_UART_2_TX_27") (pintype "bidirectional"))
    )
    (net (code "83") (name "unconnected-(U1-GP165-Pad25)") (class "Default")
      (node (ref "U1") (pin "25") (pinfunction "GP165_25") (pintype "bidirectional"))
    )
    (net (code "84") (name "unconnected-(U1-GP183_PWM3-Pad39)") (class "Default")
      (node (ref "U1") (pin "39") (pinfunction "GP183_PWM3_39") (pintype "bidirectional"))
    )
    (net (code "85") (name "unconnected-(U1-MSIC_SLP_CLK-Pad7)") (class "Default")
      (node (ref "U1") (pin "7") (pinfunction "MSIC_SLP_CLK_7") (pintype "bidirectional"))
    )
    (net (code "86") (name "unconnected-(U1-OSC_CLK_OUT_0-Pad67)") (class "Default")
      (node (ref "U1") (pin "67") (pinfunction "OSC_CLK_OUT_0_67") (pintype "bidirectional"))
    )
    (net (code "87") (name "unconnected-(U1-PSW-Pad21)") (class "Default")
      (node (ref "U1") (pin "21") (pinfunction "PSW_21") (pintype "bidirectional"))
    )
    (net (code "88") (name "unconnected-(U1-RCVR_MODE-Pad31)") (class "Default")
      (node (ref "U1") (pin "31") (pinfunction "RCVR_MODE_31") (pintype "bidirectional"))
    )
    (net (code "89") (name "unconnected-(U1-RESET_OUT#-Pad36)") (class "Default")
      (node (ref "U1") (pin "36") (pinfunction "RESET_OUT#_36") (pintype "bidirectional"))
    )
    (net (code "90") (name "unconnected-(U1-USB_DN-Pad18)") (class "Default")
      (node (ref "U1") (pin "18") (pinfunction "USB_DN_18") (pintype "bidirectional"))
    )
    (net (code "91") (name "unconnected-(U1-USB_DP-Pad16)") (class "Default")
      (node (ref "U1") (pin "16") (pinfunction "USB_DP_16") (pintype "bidirectional"))
    )
    (net (code "92") (name "unconnected-(U1-USB_ID-Pad3)") (class "Default")
      (node (ref "U1") (pin "3") (pinfunction "USB_ID_3") (pintype "bidirectional"))
    )
    (net (code "93") (name "unconnected-(U1-USB_VBUS-Pad20)") (class "Default")
      (node (ref "U1") (pin "20") (pinfunction "USB_VBUS_20") (pintype "bidirectional"))
    )
    (net (code "94") (name "unconnected-(U1-V_VAT_BKUP-Pad23)") (class "Default")
      (node (ref "U1") (pin "23") (pinfunction "V_VAT_BKUP_23") (pintype "bidirectional"))
    )
    (net (code "95") (name "unconnected-(U4-A1-Pad1)") (class "Default")
      (node (ref "U4") (pin "1") (pinfunction "A1_1") (pintype "bidirectional"))
    )
    (net (code "96") (name "unconnected-(U4-B1-Pad20)") (class "Default")
      (node (ref "U4") (pin "20") (pinfunction "B1_20") (pintype "bidirectional"))
    )
    (net (code "97") (name "unconnected-(U5-ALERT{slash}RDY-Pad2)") (class "Default")
      (node (ref "U5") (pin "2") (pinfunction "ALERT/RDY_2") (pintype "bidirectional"))
    )
    (net (code "98") (name "unconnected-(U7-BP-Pad4)") (class "Default")
      (node (ref "U7") (pin "4") (pinfunction "BP_4") (pintype "input"))
    )
    (net (code "99") (name "unconnected-(U8-CS(G)-Pad19)") (class "Default")
      (node (ref "U8") (pin "19") (pinfunction "CS(G)_19") (pintype "bidirectional"))
    )
    (net (code "100") (name "unconnected-(U8-CS(XM)-Pad20)") (class "Default")
      (node (ref "U8") (pin "20") (pinfunction "CS(XM)_20") (pintype "bidirectional"))
    )
    (net (code "101") (name "unconnected-(U8-DEN(G)-Pad10)") (class "Default")
      (node (ref "U8") (pin "10") (pinfunction "DEN(G)_10") (pintype "bidirectional"))
    )
    (net (code "102") (name "unconnected-(U8-DRDY(G)-Pad12)") (class "Default")
      (node (ref "U8") (pin "12") (pinfunction "DRDY(G)_12") (pintype "bidirectional"))
    )
    (net (code "103") (name "unconnected-(U8-INT(G)-Pad11)") (class "Default")
      (node (ref "U8") (pin "11") (pinfunction "INT(G)_11") (pintype "bidirectional"))
    )
    (net (code "104") (name "unconnected-(U8-INT1(XM)-Pad13)") (class "Default")
      (node (ref "U8") (pin "13") (pinfunction "INT1(XM)_13") (pintype "bidirectional"))
    )
    (net (code "105") (name "unconnected-(U8-INT2(XM)-Pad14)") (class "Default")
      (node (ref "U8") (pin "14") (pinfunction "INT2(XM)_14") (pintype "bidirectional"))
    )
    (net (code "106") (name "unconnected-(USB-CH-PadD+)") (class "Default")
      (node (ref "USB-CH") (pin "D+") (pinfunction "D+_D+") (pintype "bidirectional"))
    )
    (net (code "107") (name "unconnected-(USB-CH-PadD-)") (class "Default")
      (node (ref "USB-CH") (pin "D-") (pinfunction "D-_D-") (pintype "bidirectional"))
    )
  )
)
